# Device.net
KiCad netlist of a schematic drawn in EAGLE
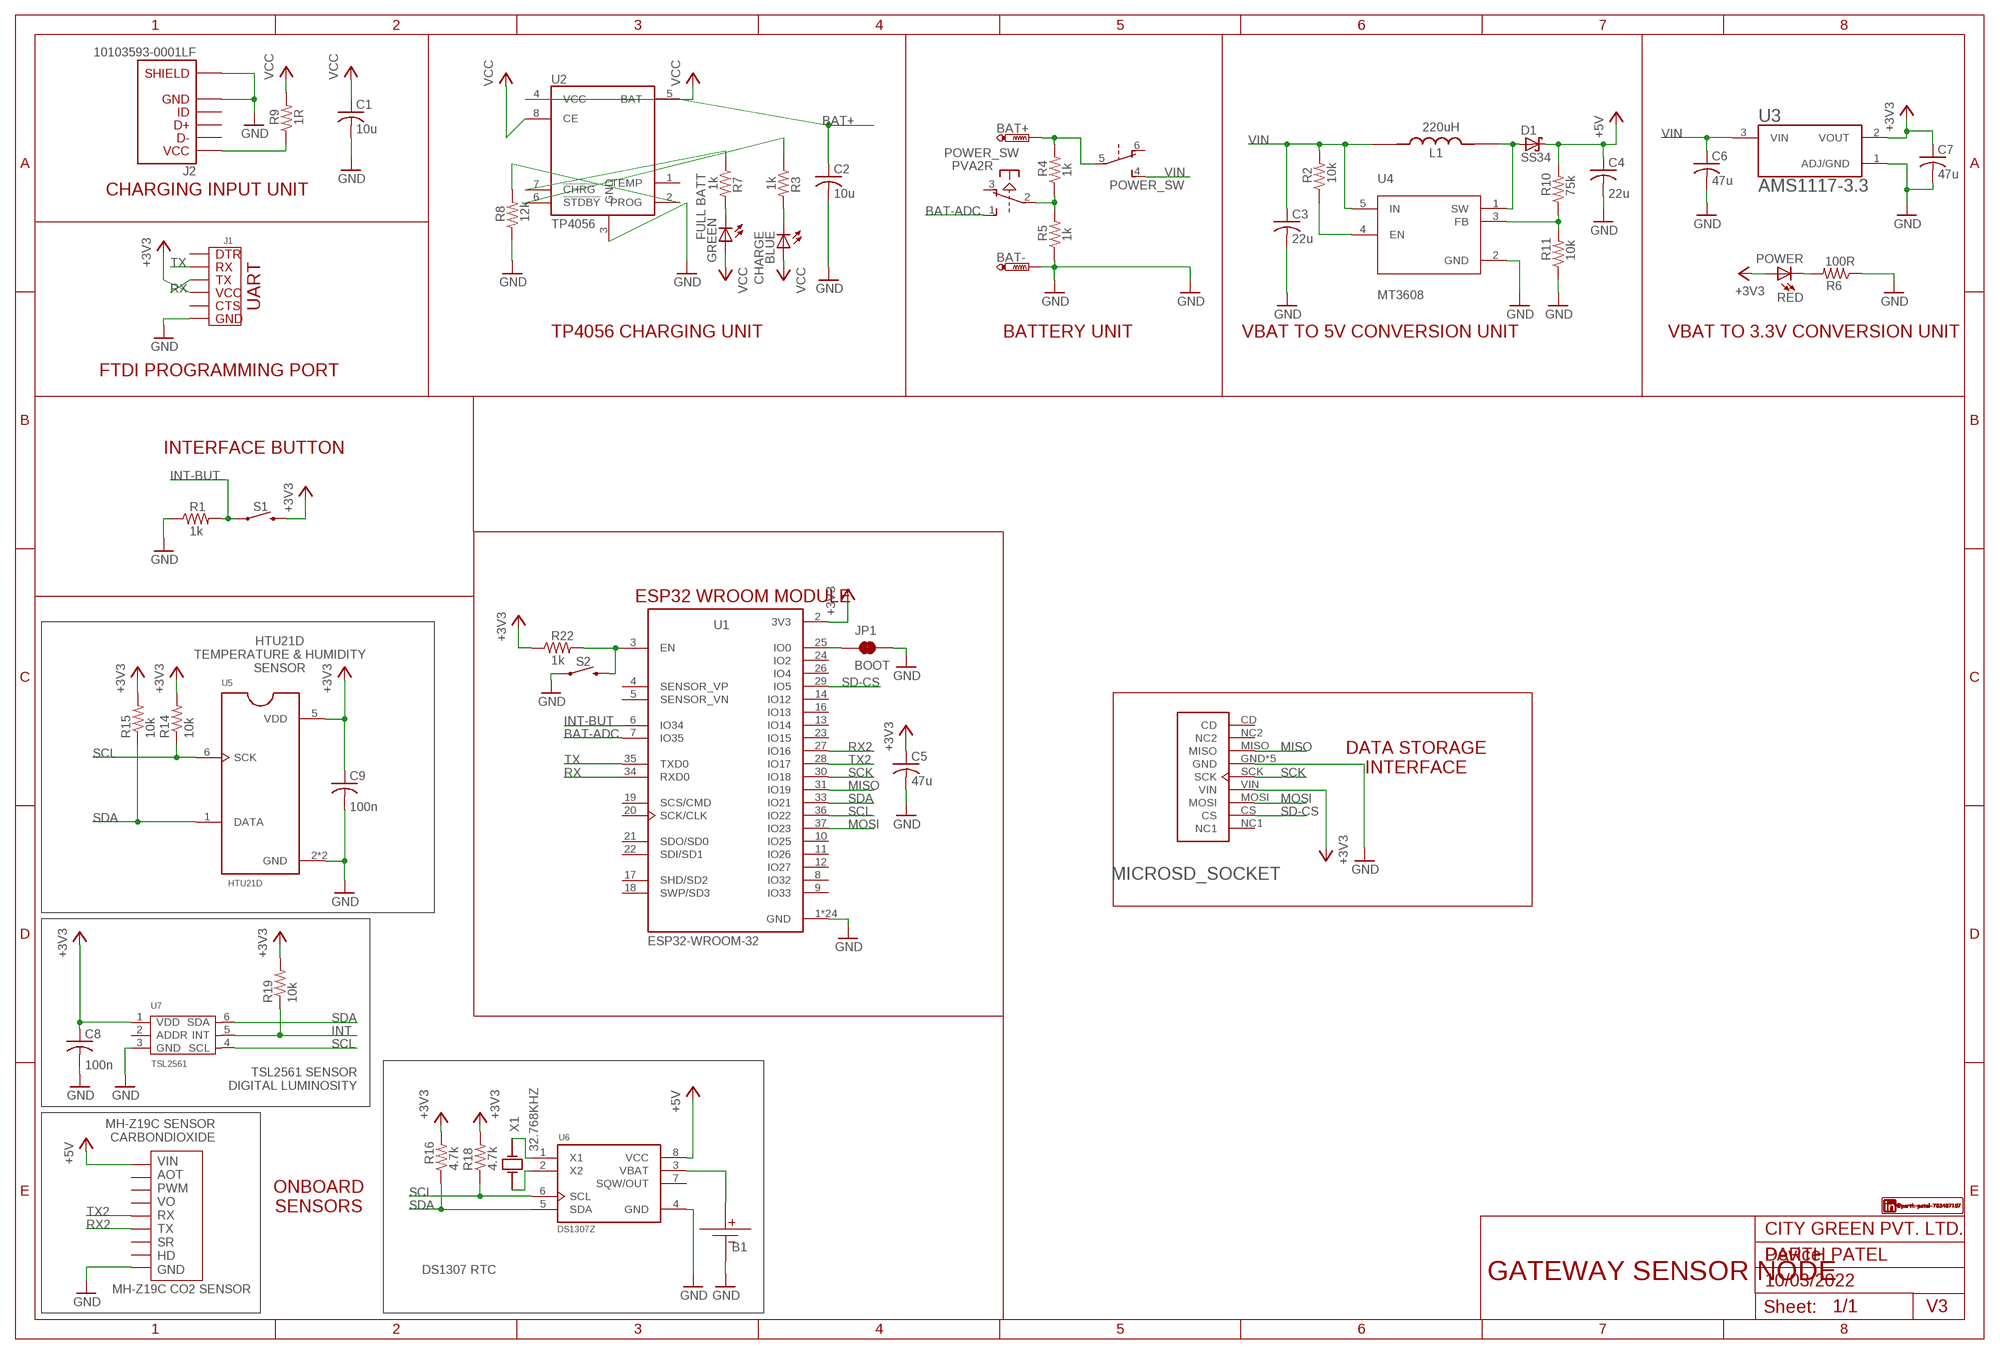
[diagram p0: schematic, sheet 1]

(export (version "E")
  (design (tool "Eeschema 10.0.6"))
  (components
    (comp (ref "B1")
      (value "CR3032-METAL")
      (footprint "eagle-import:CR2032-METAL")
      (libsource (lib "eagle-import") (part "CR3032-METAL"))
    )
    (comp (ref "BAT+")
      (value "PTR1TP20SQ")
      (footprint "eagle-import:TP20SQ")
      (libsource (lib "eagle-import") (part "PTR1TP20SQ"))
    )
    (comp (ref "BAT-")
      (value "PTR1TP20SQ")
      (footprint "eagle-import:TP20SQ")
      (libsource (lib "eagle-import") (part "PTR1TP20SQ"))
    )
    (comp (ref "BLUE")
      (value "CHARGE")
      (footprint "eagle-import:CHIP-LED0603")
      (libsource (lib "eagle-import") (part "LEDCHIP-LED0603"))
    )
    (comp (ref "C1")
      (value "10u")
      (footprint "eagle-import:C0805")
      (libsource (lib "eagle-import") (part "C-USC0805"))
    )
    (comp (ref "C2")
      (value "10u")
      (footprint "eagle-import:C0805")
      (libsource (lib "eagle-import") (part "C-USC0805"))
    )
    (comp (ref "C3")
      (value "22u")
      (footprint "eagle-import:C0805")
      (libsource (lib "eagle-import") (part "C-USC0805"))
    )
    (comp (ref "C4")
      (value "22u")
      (footprint "eagle-import:C0805")
      (libsource (lib "eagle-import") (part "C-USC0805"))
    )
    (comp (ref "C5")
      (value "47u")
      (footprint "eagle-import:C0805")
      (libsource (lib "eagle-import") (part "C-USC0805"))
    )
    (comp (ref "C6")
      (value "47u")
      (footprint "eagle-import:C0805")
      (libsource (lib "eagle-import") (part "C-USC0805"))
    )
    (comp (ref "C7")
      (value "47u")
      (footprint "eagle-import:C0805")
      (libsource (lib "eagle-import") (part "C-USC0805"))
    )
    (comp (ref "C8")
      (value "100n")
      (footprint "eagle-import:C0805")
      (libsource (lib "eagle-import") (part "C-USC0805"))
    )
    (comp (ref "C9")
      (value "100n")
      (footprint "eagle-import:C0805")
      (libsource (lib "eagle-import") (part "C-USC0805"))
    )
    (comp (ref "D1")
      (value "SS34")
      (footprint "eagle-import:DO214")
      (fields (field (name "MF") "ON Semiconductor"))
      (libsource (lib "eagle-import") (part "SS34"))
    )
    (comp (ref "GREEN")
      (value "FULL BATT")
      (footprint "eagle-import:CHIP-LED0603")
      (libsource (lib "eagle-import") (part "LEDCHIP-LED0603"))
    )
    (comp (ref "J1")
      (value "UART")
      (footprint "eagle-import:UART")
      (libsource (lib "eagle-import") (part "UART"))
    )
    (comp (ref "J2")
      (value "10103593-0001LF")
      (footprint "eagle-import:AMPHENOL_10103593-0001LF")
      (fields (field (name "MF") "AMPHENOL ICC / FCI"))
      (libsource (lib "eagle-import") (part "10103593-0001LF"))
    )
    (comp (ref "JP1")
      (value "BOOT")
      (footprint "eagle-import:SMT-JUMPER_2_NC_TRACE_NO-SILK")
      (libsource (lib "eagle-import") (part "JUMPER-SMT_2_NC_TRACE_NO-SILK"))
    )
    (comp (ref "L1")
      (value "220uH")
      (footprint "eagle-import:IND_#B953AS-221M=P3")
      (fields (field (name "MF") "Murata") (field (name "MP") "#B953AS-221M=P3"))
      (libsource (lib "eagle-import") (part "#B953AS-221M=P3"))
    )
    (comp (ref "MICROSD_SOCKET")
      (value "ST-TF-003A")
      (footprint "eagle-import:SUNTECH_ST-TF-003A")
      (fields (field (name "MF") "Suntech"))
      (libsource (lib "eagle-import") (part "ST-TF-003A"))
    )
    (comp (ref "POWER_SW")
      (value "PVA2R")
      (footprint "eagle-import:PVA2R")
      (libsource (lib "eagle-import") (part "PVA2R"))
    )
    (comp (ref "R1")
      (value "1k")
      (footprint "eagle-import:R0805")
      (libsource (lib "eagle-import") (part "R-US_R0805"))
    )
    (comp (ref "R2")
      (value "10k")
      (footprint "eagle-import:R0805")
      (libsource (lib "eagle-import") (part "R-US_R0805"))
    )
    (comp (ref "R3")
      (value "1k")
      (footprint "eagle-import:R0805")
      (libsource (lib "eagle-import") (part "R-US_R0805"))
    )
    (comp (ref "R4")
      (value "1k")
      (footprint "eagle-import:R0805")
      (libsource (lib "eagle-import") (part "R-US_R0805"))
    )
    (comp (ref "R5")
      (value "1k")
      (footprint "eagle-import:R0805")
      (libsource (lib "eagle-import") (part "R-US_R0805"))
    )
    (comp (ref "R6")
      (value "100R")
      (footprint "eagle-import:R0805")
      (libsource (lib "eagle-import") (part "R-US_R0805"))
    )
    (comp (ref "R7")
      (value "1k")
      (footprint "eagle-import:R0805")
      (libsource (lib "eagle-import") (part "R-US_R0805"))
    )
    (comp (ref "R8")
      (value "12k")
      (footprint "eagle-import:R0805")
      (libsource (lib "eagle-import") (part "R-US_R0805"))
    )
    (comp (ref "R9")
      (value "1R")
      (footprint "eagle-import:R0805")
      (libsource (lib "eagle-import") (part "R-US_R0805"))
    )
    (comp (ref "R10")
      (value "75k")
      (footprint "eagle-import:R0805")
      (libsource (lib "eagle-import") (part "R-US_R0805"))
    )
    (comp (ref "R11")
      (value "10k")
      (footprint "eagle-import:R0805")
      (libsource (lib "eagle-import") (part "R-US_R0805"))
    )
    (comp (ref "R14")
      (value "10k")
      (footprint "eagle-import:R0805")
      (libsource (lib "eagle-import") (part "R-US_R0805"))
    )
    (comp (ref "R15")
      (value "10k")
      (footprint "eagle-import:R0805")
      (libsource (lib "eagle-import") (part "R-US_R0805"))
    )
    (comp (ref "R16")
      (value "4.7k")
      (footprint "eagle-import:R0805")
      (libsource (lib "eagle-import") (part "R-US_R0805"))
    )
    (comp (ref "R18")
      (value "4.7k")
      (footprint "eagle-import:R0805")
      (libsource (lib "eagle-import") (part "R-US_R0805"))
    )
    (comp (ref "R19")
      (value "10k")
      (footprint "eagle-import:R0805")
      (libsource (lib "eagle-import") (part "R-US_R0805"))
    )
    (comp (ref "R22")
      (value "1k")
      (footprint "eagle-import:R0805")
      (libsource (lib "eagle-import") (part "R-US_R0805"))
    )
    (comp (ref "RED")
      (value "POWER")
      (footprint "eagle-import:CHIP-LED0603")
      (libsource (lib "eagle-import") (part "LEDCHIP-LED0603"))
    )
    (comp (ref "S1")
      (value "MOMENTARY-SWITCH-SPST-SMD-6.2MM-TALL")
      (footprint "eagle-import:TACTILE_SWITCH_SMD_6.2MM_TALL")
      (libsource (lib "eagle-import") (part "MOMENTARY-SWITCH-SPST-SMD-6.2MM-TALL"))
    )
    (comp (ref "S2")
      (value "RST")
      (footprint "eagle-import:TACTILE_SWITCH_SMD_6.2MM_TALL")
      (libsource (lib "eagle-import") (part "MOMENTARY-SWITCH-SPST-SMD-6.2MM-TALL"))
    )
    (comp (ref "U$1")
      (value "MH-Z19C")
      (footprint "eagle-import:MH-Z19C")
      (libsource (lib "eagle-import") (part "MH-Z19C"))
    )
    (comp (ref "U1")
      (value "ESP32-WROOM-32")
      (footprint "eagle-import:MODULE_ESP32-WROOM-32")
      (fields (field (name "MF") "Espressif Systems"))
      (libsource (lib "eagle-import") (part "ESP32-WROOM-32"))
    )
    (comp (ref "U2")
      (value "TP4056")
      (footprint "eagle-import:SOP127P600X175-9N")
      (fields (field (name "MF") "NanJing Top Power ASIC Corp."))
      (libsource (lib "eagle-import") (part "TP4056"))
    )
    (comp (ref "U3")
      (value "AMS1117-3.3")
      (footprint "eagle-import:SOT229P700X180-4N")
      (fields (field (name "MF") "AMD"))
      (libsource (lib "eagle-import") (part "AMS1117-3.3"))
    )
    (comp (ref "U4")
      (value "MT3608")
      (footprint "eagle-import:SOT95P280X145-6N")
      (fields (field (name "MF") "Aerosemi Technology Co., Ltd"))
      (libsource (lib "eagle-import") (part "MT3608"))
    )
    (comp (ref "U5")
      (value "HTU21D")
      (footprint "eagle-import:QFN100P300X300X100-7N")
      (fields (field (name "COMMENT") "CAT-HSC0004") (field (name "MF") "TE Connectivity"))
      (libsource (lib "eagle-import") (part "HTU21D"))
    )
    (comp (ref "U6")
      (value "DS1307Z")
      (footprint "eagle-import:SOIC127P600X175-8N")
      (fields (field (name "MF") "Maxim Integrated"))
      (libsource (lib "eagle-import") (part "DS1307Z"))
    )
    (comp (ref "U7")
      (value "TSL2561")
      (footprint "eagle-import:TMB6-1.55-3.8X2.6MM")
      (fields (field (name "MF") "ams") (field (name "MP") "TSL2561T"))
      (libsource (lib "eagle-import") (part "OPTICAL-TSL2561T(6P-3.8X2.6MM)"))
    )
    (comp (ref "X1")
      (value "32.768KHZ")
      (footprint "eagle-import:XTAL_AB38T-32.768KHZ")
      (fields (field (name "MF") "Abracon") (field (name "MP") "AB38T-32.768KHZ"))
      (libsource (lib "eagle-import") (part "AB38T-32.768KHZ"))
    )
  )
  (nets
    (net (code "1") (name "+3V3") (class "Default")
      (node (ref "C5") (pin "1") (pinfunction "1_1") (pintype "passive"))
      (node (ref "C7") (pin "1") (pinfunction "1_1") (pintype "passive"))
      (node (ref "C8") (pin "1") (pinfunction "1_1") (pintype "passive"))
      (node (ref "C9") (pin "1") (pinfunction "1_1") (pintype "passive"))
      (node (ref "J1") (pin "VCC") (pinfunction "VCC_VCC") (pintype "bidirectional"))
      (node (ref "MICROSD_SOCKET") (pin "VIN") (pinfunction "VIN_VIN") (pintype "bidirectional"))
      (node (ref "R14") (pin "2") (pinfunction "2_2") (pintype "passive"))
      (node (ref "R15") (pin "2") (pinfunction "2_2") (pintype "passive"))
      (node (ref "R16") (pin "2") (pinfunction "2_2") (pintype "passive"))
      (node (ref "R18") (pin "2") (pinfunction "2_2") (pintype "passive"))
      (node (ref "R19") (pin "2") (pinfunction "2_2") (pintype "passive"))
      (node (ref "R22") (pin "1") (pinfunction "1_1") (pintype "passive"))
      (node (ref "RED") (pin "A") (pinfunction "A_A") (pintype "passive"))
      (node (ref "S1") (pin "B2") (pinfunction "2_B2") (pintype "passive"))
      (node (ref "U1") (pin "2") (pinfunction "3V3_2") (pintype "power_in"))
      (node (ref "U3") (pin "2") (pinfunction "VOUT_2") (pintype "output"))
      (node (ref "U5") (pin "5") (pinfunction "VDD_5") (pintype "power_in"))
      (node (ref "U7") (pin "1") (pinfunction "VDD_1") (pintype "power_in"))
    )
    (net (code "2") (name "+5V") (class "Default")
      (node (ref "C4") (pin "1") (pinfunction "1_1") (pintype "passive"))
      (node (ref "D1") (pin "C") (pinfunction "C_C") (pintype "passive"))
      (node (ref "R10") (pin "2") (pinfunction "2_2") (pintype "passive"))
      (node (ref "U$1") (pin "VIN") (pinfunction "VIN_VIN") (pintype "bidirectional"))
      (node (ref "U6") (pin "8") (pinfunction "VCC_8") (pintype "power_in"))
    )
    (net (code "3") (name "/BAT+") (class "Default")
      (node (ref "BAT+") (pin "TP") (pinfunction "TP_TP") (pintype "input"))
      (node (ref "C2") (pin "1") (pinfunction "1_1") (pintype "passive"))
      (node (ref "POWER_SW") (pin "5") (pinfunction "P_5") (pintype "passive"))
      (node (ref "R4") (pin "2") (pinfunction "2_2") (pintype "passive"))
      (node (ref "U2") (pin "5") (pinfunction "BAT_5") (pintype "output"))
    )
    (net (code "4") (name "/BAT-ADC") (class "Default")
      (node (ref "POWER_SW") (pin "1") (pinfunction "S_1") (pintype "passive"))
      (node (ref "U1") (pin "7") (pinfunction "IO35_7") (pintype "input"))
    )
    (net (code "5") (name "/INT") (class "Default")
      (node (ref "R19") (pin "1") (pinfunction "1_1") (pintype "passive"))
      (node (ref "U7") (pin "5") (pinfunction "INT_5") (pintype "output"))
    )
    (net (code "6") (name "/INT-BUT") (class "Default")
      (node (ref "R1") (pin "2") (pinfunction "2_2") (pintype "passive"))
      (node (ref "S1") (pin "A2") (pinfunction "1_A2") (pintype "passive"))
      (node (ref "U1") (pin "6") (pinfunction "IO34_6") (pintype "input"))
    )
    (net (code "7") (name "/MISO") (class "Default")
      (node (ref "MICROSD_SOCKET") (pin "MISO") (pinfunction "MISO_MISO") (pintype "bidirectional"))
      (node (ref "U1") (pin "31") (pinfunction "IO19_31") (pintype "bidirectional"))
    )
    (net (code "8") (name "/MOSI") (class "Default")
      (node (ref "MICROSD_SOCKET") (pin "MOSI") (pinfunction "MOSI_MOSI") (pintype "input"))
      (node (ref "U1") (pin "37") (pinfunction "IO23_37") (pintype "bidirectional"))
    )
    (net (code "9") (name "/RX") (class "Default")
      (node (ref "J1") (pin "TX") (pinfunction "TX_TX") (pintype "bidirectional"))
      (node (ref "U1") (pin "34") (pinfunction "RXD0_34") (pintype "bidirectional"))
    )
    (net (code "10") (name "/RX2") (class "Default")
      (node (ref "U$1") (pin "TX") (pinfunction "TX_TX") (pintype "bidirectional"))
      (node (ref "U1") (pin "27") (pinfunction "IO16_27") (pintype "bidirectional"))
    )
    (net (code "11") (name "/SCK") (class "Default")
      (node (ref "MICROSD_SOCKET") (pin "SCK") (pinfunction "SCK_SCK") (pintype "input"))
      (node (ref "U1") (pin "30") (pinfunction "IO18_30") (pintype "bidirectional"))
    )
    (net (code "12") (name "/SCL") (class "Default")
      (node (ref "R14") (pin "1") (pinfunction "1_1") (pintype "passive"))
      (node (ref "R18") (pin "1") (pinfunction "1_1") (pintype "passive"))
      (node (ref "U1") (pin "36") (pinfunction "IO22_36") (pintype "bidirectional"))
      (node (ref "U5") (pin "6") (pinfunction "SCK_6") (pintype "input"))
      (node (ref "U6") (pin "6") (pinfunction "SCL_6") (pintype "input"))
      (node (ref "U7") (pin "4") (pinfunction "SCL_4") (pintype "input"))
    )
    (net (code "13") (name "/SD-CS") (class "Default")
      (node (ref "MICROSD_SOCKET") (pin "CS") (pinfunction "CS_CS") (pintype "bidirectional"))
      (node (ref "U1") (pin "29") (pinfunction "IO5_29") (pintype "bidirectional"))
    )
    (net (code "14") (name "/SDA") (class "Default")
      (node (ref "R15") (pin "1") (pinfunction "1_1") (pintype "passive"))
      (node (ref "R16") (pin "1") (pinfunction "1_1") (pintype "passive"))
      (node (ref "U1") (pin "33") (pinfunction "IO21_33") (pintype "bidirectional"))
      (node (ref "U5") (pin "1") (pinfunction "DATA_1") (pintype "bidirectional"))
      (node (ref "U6") (pin "5") (pinfunction "SDA_5") (pintype "bidirectional"))
      (node (ref "U7") (pin "6") (pinfunction "SDA_6") (pintype "bidirectional"))
    )
    (net (code "15") (name "/TX") (class "Default")
      (node (ref "J1") (pin "RX") (pinfunction "RX_RX") (pintype "bidirectional"))
      (node (ref "U1") (pin "35") (pinfunction "TXD0_35") (pintype "bidirectional"))
    )
    (net (code "16") (name "/TX2") (class "Default")
      (node (ref "U$1") (pin "RX") (pinfunction "RX_RX") (pintype "bidirectional"))
      (node (ref "U1") (pin "28") (pinfunction "IO17_28") (pintype "bidirectional"))
    )
    (net (code "17") (name "/VIN") (class "Default")
      (node (ref "C3") (pin "1") (pinfunction "1_1") (pintype "passive"))
      (node (ref "C6") (pin "1") (pinfunction "1_1") (pintype "passive"))
      (node (ref "L1") (pin "1") (pinfunction "1_1") (pintype "passive"))
      (node (ref "POWER_SW") (pin "4") (pinfunction "S_4") (pintype "passive"))
      (node (ref "R2") (pin "2") (pinfunction "2_2") (pintype "passive"))
      (node (ref "U3") (pin "3") (pinfunction "VIN_3") (pintype "input"))
      (node (ref "U4") (pin "5") (pinfunction "IN_5") (pintype "input"))
    )
    (net (code "18") (name "GND") (class "Default")
      (node (ref "B1") (pin "-VE1") (pinfunction "-VE_-VE1") (pintype "bidirectional"))
      (node (ref "B1") (pin "-VE2") (pinfunction "-VE_-VE2") (pintype "bidirectional"))
      (node (ref "BAT-") (pin "TP") (pinfunction "TP_TP") (pintype "input"))
      (node (ref "C1") (pin "2") (pinfunction "2_2") (pintype "passive"))
      (node (ref "C2") (pin "2") (pinfunction "2_2") (pintype "passive"))
      (node (ref "C3") (pin "2") (pinfunction "2_2") (pintype "passive"))
      (node (ref "C4") (pin "2") (pinfunction "2_2") (pintype "passive"))
      (node (ref "C5") (pin "2") (pinfunction "2_2") (pintype "passive"))
      (node (ref "C6") (pin "2") (pinfunction "2_2") (pintype "passive"))
      (node (ref "C7") (pin "2") (pinfunction "2_2") (pintype "passive"))
      (node (ref "C8") (pin "2") (pinfunction "2_2") (pintype "passive"))
      (node (ref "C9") (pin "2") (pinfunction "2_2") (pintype "passive"))
      (node (ref "J1") (pin "GND") (pinfunction "GND_GND") (pintype "bidirectional"))
      (node (ref "J2") (pin "5") (pinfunction "5_5") (pintype "passive"))
      (node (ref "J2") (pin "S1") (pinfunction "SHIELD_S1") (pintype "passive"))
      (node (ref "J2") (pin "S2") (pinfunction "SHIELD_S2") (pintype "passive"))
      (node (ref "J2") (pin "S3") (pinfunction "SHIELD_S3") (pintype "passive"))
      (node (ref "J2") (pin "S4") (pinfunction "SHIELD_S4") (pintype "passive"))
      (node (ref "J2") (pin "S5") (pinfunction "SHIELD_S5") (pintype "passive"))
      (node (ref "J2") (pin "S6") (pinfunction "SHIELD_S6") (pintype "passive"))
      (node (ref "JP1") (pin "2") (pinfunction "2_2") (pintype "passive"))
      (node (ref "MICROSD_SOCKET") (pin "GND") (pinfunction "GND_GND") (pintype "power_in"))
      (node (ref "MICROSD_SOCKET") (pin "GND2") (pinfunction "GND_GND2") (pintype "power_in"))
      (node (ref "MICROSD_SOCKET") (pin "GND3") (pinfunction "GND_GND3") (pintype "power_in"))
      (node (ref "MICROSD_SOCKET") (pin "GND4") (pinfunction "GND_GND4") (pintype "power_in"))
      (node (ref "MICROSD_SOCKET") (pin "GND5") (pinfunction "GND_GND5") (pintype "power_in"))
      (node (ref "R1") (pin "1") (pinfunction "1_1") (pintype "passive"))
      (node (ref "R11") (pin "1") (pinfunction "1_1") (pintype "passive"))
      (node (ref "R5") (pin "1") (pinfunction "1_1") (pintype "passive"))
      (node (ref "R6") (pin "1") (pinfunction "1_1") (pintype "passive"))
      (node (ref "R8") (pin "1") (pinfunction "1_1") (pintype "passive"))
      (node (ref "S2") (pin "A2") (pinfunction "1_A2") (pintype "passive"))
      (node (ref "U$1") (pin "GND") (pinfunction "GND_GND") (pintype "bidirectional"))
      (node (ref "U1") (pin "1") (pinfunction "GND_1") (pintype "power_in"))
      (node (ref "U1") (pin "15") (pinfunction "GND_15") (pintype "power_in"))
      (node (ref "U1") (pin "38") (pinfunction "GND_38") (pintype "power_in"))
      (node (ref "U1") (pin "39_1") (pinfunction "GND_39_1") (pintype "power_in"))
      (node (ref "U1") (pin "39_10") (pinfunction "GND_39_10") (pintype "power_in"))
      (node (ref "U1") (pin "39_11") (pinfunction "GND_39_11") (pintype "power_in"))
      (node (ref "U1") (pin "39_12") (pinfunction "GND_39_12") (pintype "power_in"))
      (node (ref "U1") (pin "39_13") (pinfunction "GND_39_13") (pintype "power_in"))
      (node (ref "U1") (pin "39_14") (pinfunction "GND_39_14") (pintype "power_in"))
      (node (ref "U1") (pin "39_15") (pinfunction "GND_39_15") (pintype "power_in"))
      (node (ref "U1") (pin "39_16") (pinfunction "GND_39_16") (pintype "power_in"))
      (node (ref "U1") (pin "39_17") (pinfunction "GND_39_17") (pintype "power_in"))
      (node (ref "U1") (pin "39_18") (pinfunction "GND_39_18") (pintype "power_in"))
      (node (ref "U1") (pin "39_19") (pinfunction "GND_39_19") (pintype "power_in"))
      (node (ref "U1") (pin "39_2") (pinfunction "GND_39_2") (pintype "power_in"))
      (node (ref "U1") (pin "39_20") (pinfunction "GND_39_20") (pintype "power_in"))
      (node (ref "U1") (pin "39_21") (pinfunction "GND_39_21") (pintype "power_in"))
      (node (ref "U1") (pin "39_3") (pinfunction "GND_39_3") (pintype "power_in"))
      (node (ref "U1") (pin "39_4") (pinfunction "GND_39_4") (pintype "power_in"))
      (node (ref "U1") (pin "39_5") (pinfunction "GND_39_5") (pintype "power_in"))
      (node (ref "U1") (pin "39_6") (pinfunction "GND_39_6") (pintype "power_in"))
      (node (ref "U1") (pin "39_7") (pinfunction "GND_39_7") (pintype "power_in"))
      (node (ref "U1") (pin "39_8") (pinfunction "GND_39_8") (pintype "power_in"))
      (node (ref "U1") (pin "39_9") (pinfunction "GND_39_9") (pintype "power_in"))
      (node (ref "U2") (pin "3") (pinfunction "GND_3") (pintype "power_in"))
      (node (ref "U3") (pin "1") (pinfunction "ADJ/GND_1") (pintype "power_in"))
      (node (ref "U4") (pin "2") (pinfunction "GND_2") (pintype "power_in"))
      (node (ref "U5") (pin "2") (pinfunction "GND_2") (pintype "passive"))
      (node (ref "U5") (pin "PAD") (pinfunction "GND_PAD") (pintype "passive"))
      (node (ref "U6") (pin "4") (pinfunction "GND_4") (pintype "power_in"))
      (node (ref "U7") (pin "3") (pinfunction "GND_3") (pintype "power_in"))
    )
    (net (code "19") (name "Net-(BLUE-PadC)") (class "Default")
      (node (ref "BLUE") (pin "C") (pinfunction "C_C") (pintype "passive"))
      (node (ref "R3") (pin "2") (pinfunction "2_2") (pintype "passive"))
    )
    (net (code "20") (name "Net-(GREEN-PadC)") (class "Default")
      (node (ref "GREEN") (pin "C") (pinfunction "C_C") (pintype "passive"))
      (node (ref "R7") (pin "2") (pinfunction "2_2") (pintype "passive"))
    )
    (net (code "21") (name "Net-(J2-Pad1)") (class "Default")
      (node (ref "J2") (pin "1") (pinfunction "1_1") (pintype "passive"))
      (node (ref "R9") (pin "1") (pinfunction "1_1") (pintype "passive"))
    )
    (net (code "22") (name "Net-(POWER_SWA-P)") (class "Default")
      (node (ref "POWER_SW") (pin "2") (pinfunction "P_2") (pintype "passive"))
      (node (ref "R4") (pin "1") (pinfunction "1_1") (pintype "passive"))
      (node (ref "R5") (pin "2") (pinfunction "2_2") (pintype "passive"))
    )
    (net (code "23") (name "Net-(R6-Pad2)") (class "Default")
      (node (ref "R6") (pin "2") (pinfunction "2_2") (pintype "passive"))
      (node (ref "RED") (pin "C") (pinfunction "C_C") (pintype "passive"))
    )
    (net (code "24") (name "Net-(S2-2)") (class "Default")
      (node (ref "R22") (pin "2") (pinfunction "2_2") (pintype "passive"))
      (node (ref "S2") (pin "B2") (pinfunction "2_B2") (pintype "passive"))
      (node (ref "U1") (pin "3") (pinfunction "EN_3") (pintype "input"))
    )
    (net (code "25") (name "Net-(U1-IO0)") (class "Default")
      (node (ref "JP1") (pin "1") (pinfunction "1_1") (pintype "passive"))
      (node (ref "U1") (pin "25") (pinfunction "IO0_25") (pintype "bidirectional"))
    )
    (net (code "26") (name "Net-(U2-PROG)") (class "Default")
      (node (ref "R8") (pin "2") (pinfunction "2_2") (pintype "passive"))
      (node (ref "U2") (pin "2") (pinfunction "PROG_2") (pintype "bidirectional"))
    )
    (net (code "27") (name "Net-(U2-~{CHRG})") (class "Default")
      (node (ref "R7") (pin "1") (pinfunction "1_1") (pintype "passive"))
      (node (ref "U2") (pin "7") (pinfunction "~{CHRG}_7") (pintype "output"))
    )
    (net (code "28") (name "Net-(U2-~{STDBY})") (class "Default")
      (node (ref "R3") (pin "1") (pinfunction "1_1") (pintype "passive"))
      (node (ref "U2") (pin "6") (pinfunction "~{STDBY}_6") (pintype "output"))
    )
    (net (code "29") (name "Net-(U4-EN)") (class "Default")
      (node (ref "R2") (pin "1") (pinfunction "1_1") (pintype "passive"))
      (node (ref "U4") (pin "4") (pinfunction "EN_4") (pintype "input"))
    )
    (net (code "30") (name "Net-(U4-FB)") (class "Default")
      (node (ref "R10") (pin "1") (pinfunction "1_1") (pintype "passive"))
      (node (ref "R11") (pin "2") (pinfunction "2_2") (pintype "passive"))
      (node (ref "U4") (pin "3") (pinfunction "FB_3") (pintype "input"))
    )
    (net (code "31") (name "Net-(U4-SW)") (class "Default")
      (node (ref "D1") (pin "A") (pinfunction "A_A") (pintype "passive"))
      (node (ref "L1") (pin "2") (pinfunction "2_2") (pintype "passive"))
      (node (ref "U4") (pin "1") (pinfunction "SW_1") (pintype "output"))
    )
    (net (code "32") (name "Net-(U6-VBAT)") (class "Default")
      (node (ref "B1") (pin "+VE") (pinfunction "+VE_+VE") (pintype "bidirectional"))
      (node (ref "U6") (pin "3") (pinfunction "VBAT_3") (pintype "power_in"))
    )
    (net (code "33") (name "Net-(U6-X1)") (class "Default")
      (node (ref "U6") (pin "1") (pinfunction "X1_1") (pintype "input"))
      (node (ref "X1") (pin "2") (pinfunction "2_2") (pintype "passive"))
    )
    (net (code "34") (name "Net-(U6-X2)") (class "Default")
      (node (ref "U6") (pin "2") (pinfunction "X2_2") (pintype "input"))
      (node (ref "X1") (pin "1") (pinfunction "1_1") (pintype "passive"))
    )
    (net (code "35") (name "VCC") (class "Default")
      (node (ref "BLUE") (pin "A") (pinfunction "A_A") (pintype "passive"))
      (node (ref "C1") (pin "1") (pinfunction "1_1") (pintype "passive"))
      (node (ref "GREEN") (pin "A") (pinfunction "A_A") (pintype "passive"))
      (node (ref "R9") (pin "2") (pinfunction "2_2") (pintype "passive"))
      (node (ref "U2") (pin "4") (pinfunction "VCC_4") (pintype "power_in"))
      (node (ref "U2") (pin "8") (pinfunction "CE_8") (pintype "input"))
    )
    (net (code "36") (name "unconnected-(J1-PadCTS)") (class "Default")
      (node (ref "J1") (pin "CTS") (pinfunction "CTS_CTS") (pintype "bidirectional"))
    )
    (net (code "37") (name "unconnected-(J1-PadDTR)") (class "Default")
      (node (ref "J1") (pin "DTR") (pinfunction "DTR_DTR") (pintype "bidirectional"))
    )
    (net (code "38") (name "unconnected-(J2-Pad2)") (class "Default")
      (node (ref "J2") (pin "2") (pinfunction "2_2") (pintype "passive"))
    )
    (net (code "39") (name "unconnected-(J2-Pad3)") (class "Default")
      (node (ref "J2") (pin "3") (pinfunction "3_3") (pintype "passive"))
    )
    (net (code "40") (name "unconnected-(J2-Pad4)") (class "Default")
      (node (ref "J2") (pin "4") (pinfunction "4_4") (pintype "passive"))
    )
    (net (code "41") (name "unconnected-(MICROSD_SOCKET-PadCD)") (class "Default")
      (node (ref "MICROSD_SOCKET") (pin "CD") (pinfunction "CD_CD") (pintype "bidirectional"))
    )
    (net (code "42") (name "unconnected-(MICROSD_SOCKET-PadNC1)") (class "Default")
      (node (ref "MICROSD_SOCKET") (pin "NC1") (pinfunction "NC1_NC1") (pintype "bidirectional"))
    )
    (net (code "43") (name "unconnected-(MICROSD_SOCKET-PadNC2)") (class "Default")
      (node (ref "MICROSD_SOCKET") (pin "NC2") (pinfunction "NC2_NC2") (pintype "passive"))
    )
    (net (code "44") (name "unconnected-(POWER_SWA-O-Pad3)") (class "Default")
      (node (ref "POWER_SW") (pin "3") (pinfunction "O_3") (pintype "passive"))
    )
    (net (code "45") (name "unconnected-(POWER_SWB-O-Pad6)") (class "Default")
      (node (ref "POWER_SW") (pin "6") (pinfunction "O_6") (pintype "passive"))
    )
    (net (code "46") (name "unconnected-(U$1-PadAOT)") (class "Default")
      (node (ref "U$1") (pin "AOT") (pinfunction "AOT_AOT") (pintype "bidirectional"))
    )
    (net (code "47") (name "unconnected-(U$1-PadHD)") (class "Default")
      (node (ref "U$1") (pin "HD") (pinfunction "HD_HD") (pintype "bidirectional"))
    )
    (net (code "48") (name "unconnected-(U$1-PadPWM)") (class "Default")
      (node (ref "U$1") (pin "PWM") (pinfunction "PWM_PWM") (pintype "bidirectional"))
    )
    (net (code "49") (name "unconnected-(U$1-PadSR)") (class "Default")
      (node (ref "U$1") (pin "SR") (pinfunction "SR_SR") (pintype "bidirectional"))
    )
    (net (code "50") (name "unconnected-(U$1-PadVO)") (class "Default")
      (node (ref "U$1") (pin "VO") (pinfunction "VO_VO") (pintype "bidirectional"))
    )
    (net (code "51") (name "unconnected-(U1-IO2-Pad24)") (class "Default")
      (node (ref "U1") (pin "24") (pinfunction "IO2_24") (pintype "bidirectional"))
    )
    (net (code "52") (name "unconnected-(U1-IO4-Pad26)") (class "Default")
      (node (ref "U1") (pin "26") (pinfunction "IO4_26") (pintype "bidirectional"))
    )
    (net (code "53") (name "unconnected-(U1-IO12-Pad14)") (class "Default")
      (node (ref "U1") (pin "14") (pinfunction "IO12_14") (pintype "bidirectional"))
    )
    (net (code "54") (name "unconnected-(U1-IO13-Pad16)") (class "Default")
      (node (ref "U1") (pin "16") (pinfunction "IO13_16") (pintype "bidirectional"))
    )
    (net (code "55") (name "unconnected-(U1-IO14-Pad13)") (class "Default")
      (node (ref "U1") (pin "13") (pinfunction "IO14_13") (pintype "bidirectional"))
    )
    (net (code "56") (name "unconnected-(U1-IO15-Pad23)") (class "Default")
      (node (ref "U1") (pin "23") (pinfunction "IO15_23") (pintype "bidirectional"))
    )
    (net (code "57") (name "unconnected-(U1-IO25-Pad10)") (class "Default")
      (node (ref "U1") (pin "10") (pinfunction "IO25_10") (pintype "bidirectional"))
    )
    (net (code "58") (name "unconnected-(U1-IO26-Pad11)") (class "Default")
      (node (ref "U1") (pin "11") (pinfunction "IO26_11") (pintype "bidirectional"))
    )
    (net (code "59") (name "unconnected-(U1-IO27-Pad12)") (class "Default")
      (node (ref "U1") (pin "12") (pinfunction "IO27_12") (pintype "bidirectional"))
    )
    (net (code "60") (name "unconnected-(U1-IO32-Pad8)") (class "Default")
      (node (ref "U1") (pin "8") (pinfunction "IO32_8") (pintype "bidirectional"))
    )
    (net (code "61") (name "unconnected-(U1-IO33-Pad9)") (class "Default")
      (node (ref "U1") (pin "9") (pinfunction "IO33_9") (pintype "bidirectional"))
    )
    (net (code "62") (name "unconnected-(U1-SCK{slash}CLK-Pad20)") (class "Default")
      (node (ref "U1") (pin "20") (pinfunction "SCK/CLK_20") (pintype "bidirectional"))
    )
    (net (code "63") (name "unconnected-(U1-SCS{slash}CMD-Pad19)") (class "Default")
      (node (ref "U1") (pin "19") (pinfunction "SCS/CMD_19") (pintype "bidirectional"))
    )
    (net (code "64") (name "unconnected-(U1-SDI{slash}SD1-Pad22)") (class "Default")
      (node (ref "U1") (pin "22") (pinfunction "SDI/SD1_22") (pintype "bidirectional"))
    )
    (net (code "65") (name "unconnected-(U1-SDO{slash}SD0-Pad21)") (class "Default")
      (node (ref "U1") (pin "21") (pinfunction "SDO/SD0_21") (pintype "bidirectional"))
    )
    (net (code "66") (name "unconnected-(U1-SENSOR_VN-Pad5)") (class "Default")
      (node (ref "U1") (pin "5") (pinfunction "SENSOR_VN_5") (pintype "input"))
    )
    (net (code "67") (name "unconnected-(U1-SENSOR_VP-Pad4)") (class "Default")
      (node (ref "U1") (pin "4") (pinfunction "SENSOR_VP_4") (pintype "input"))
    )
    (net (code "68") (name "unconnected-(U1-SHD{slash}SD2-Pad17)") (class "Default")
      (node (ref "U1") (pin "17") (pinfunction "SHD/SD2_17") (pintype "bidirectional"))
    )
    (net (code "69") (name "unconnected-(U1-SWP{slash}SD3-Pad18)") (class "Default")
      (node (ref "U1") (pin "18") (pinfunction "SWP/SD3_18") (pintype "bidirectional"))
    )
    (net (code "70") (name "unconnected-(U2-TEMP-Pad1)") (class "Default")
      (node (ref "U2") (pin "1") (pinfunction "TEMP_1") (pintype "input"))
    )
    (net (code "71") (name "unconnected-(U6-SQW{slash}OUT-Pad7)") (class "Default")
      (node (ref "U6") (pin "7") (pinfunction "SQW/OUT_7") (pintype "output"))
    )
    (net (code "72") (name "unconnected-(U7-ADDR-Pad2)") (class "Default")
      (node (ref "U7") (pin "2") (pinfunction "ADDR_2") (pintype "input"))
    )
  )
)
